# FPGA.net
KiCad netlist of a schematic drawn in Altium Designer
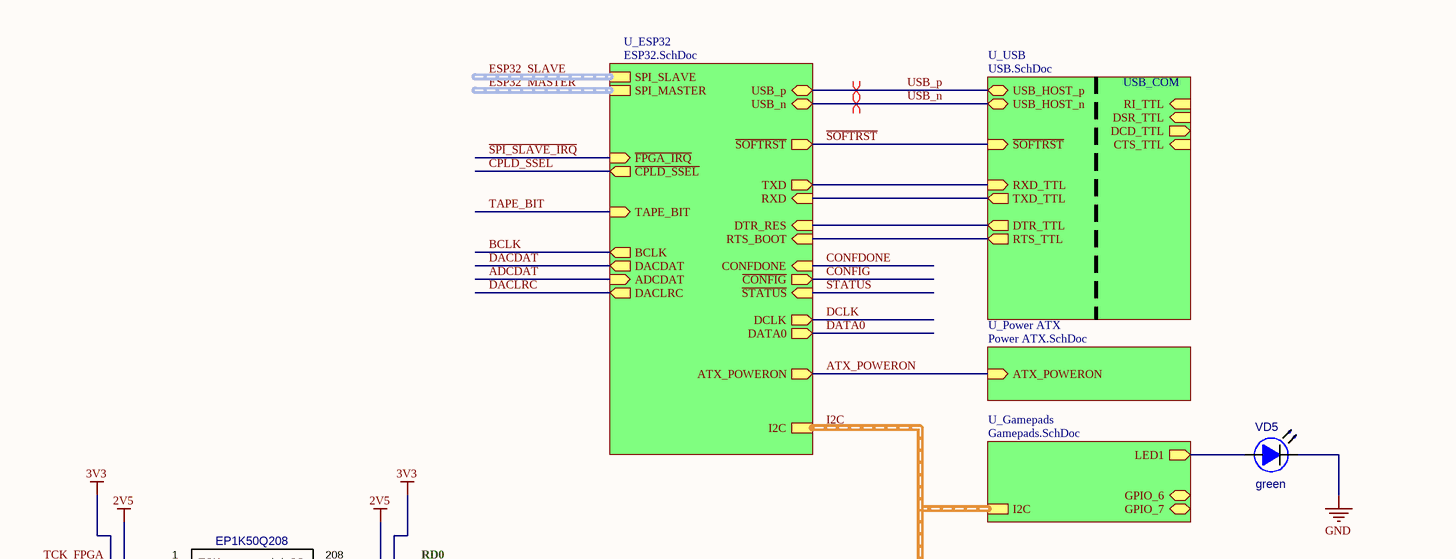
[diagram p0: FPGA.SchDoc, top]
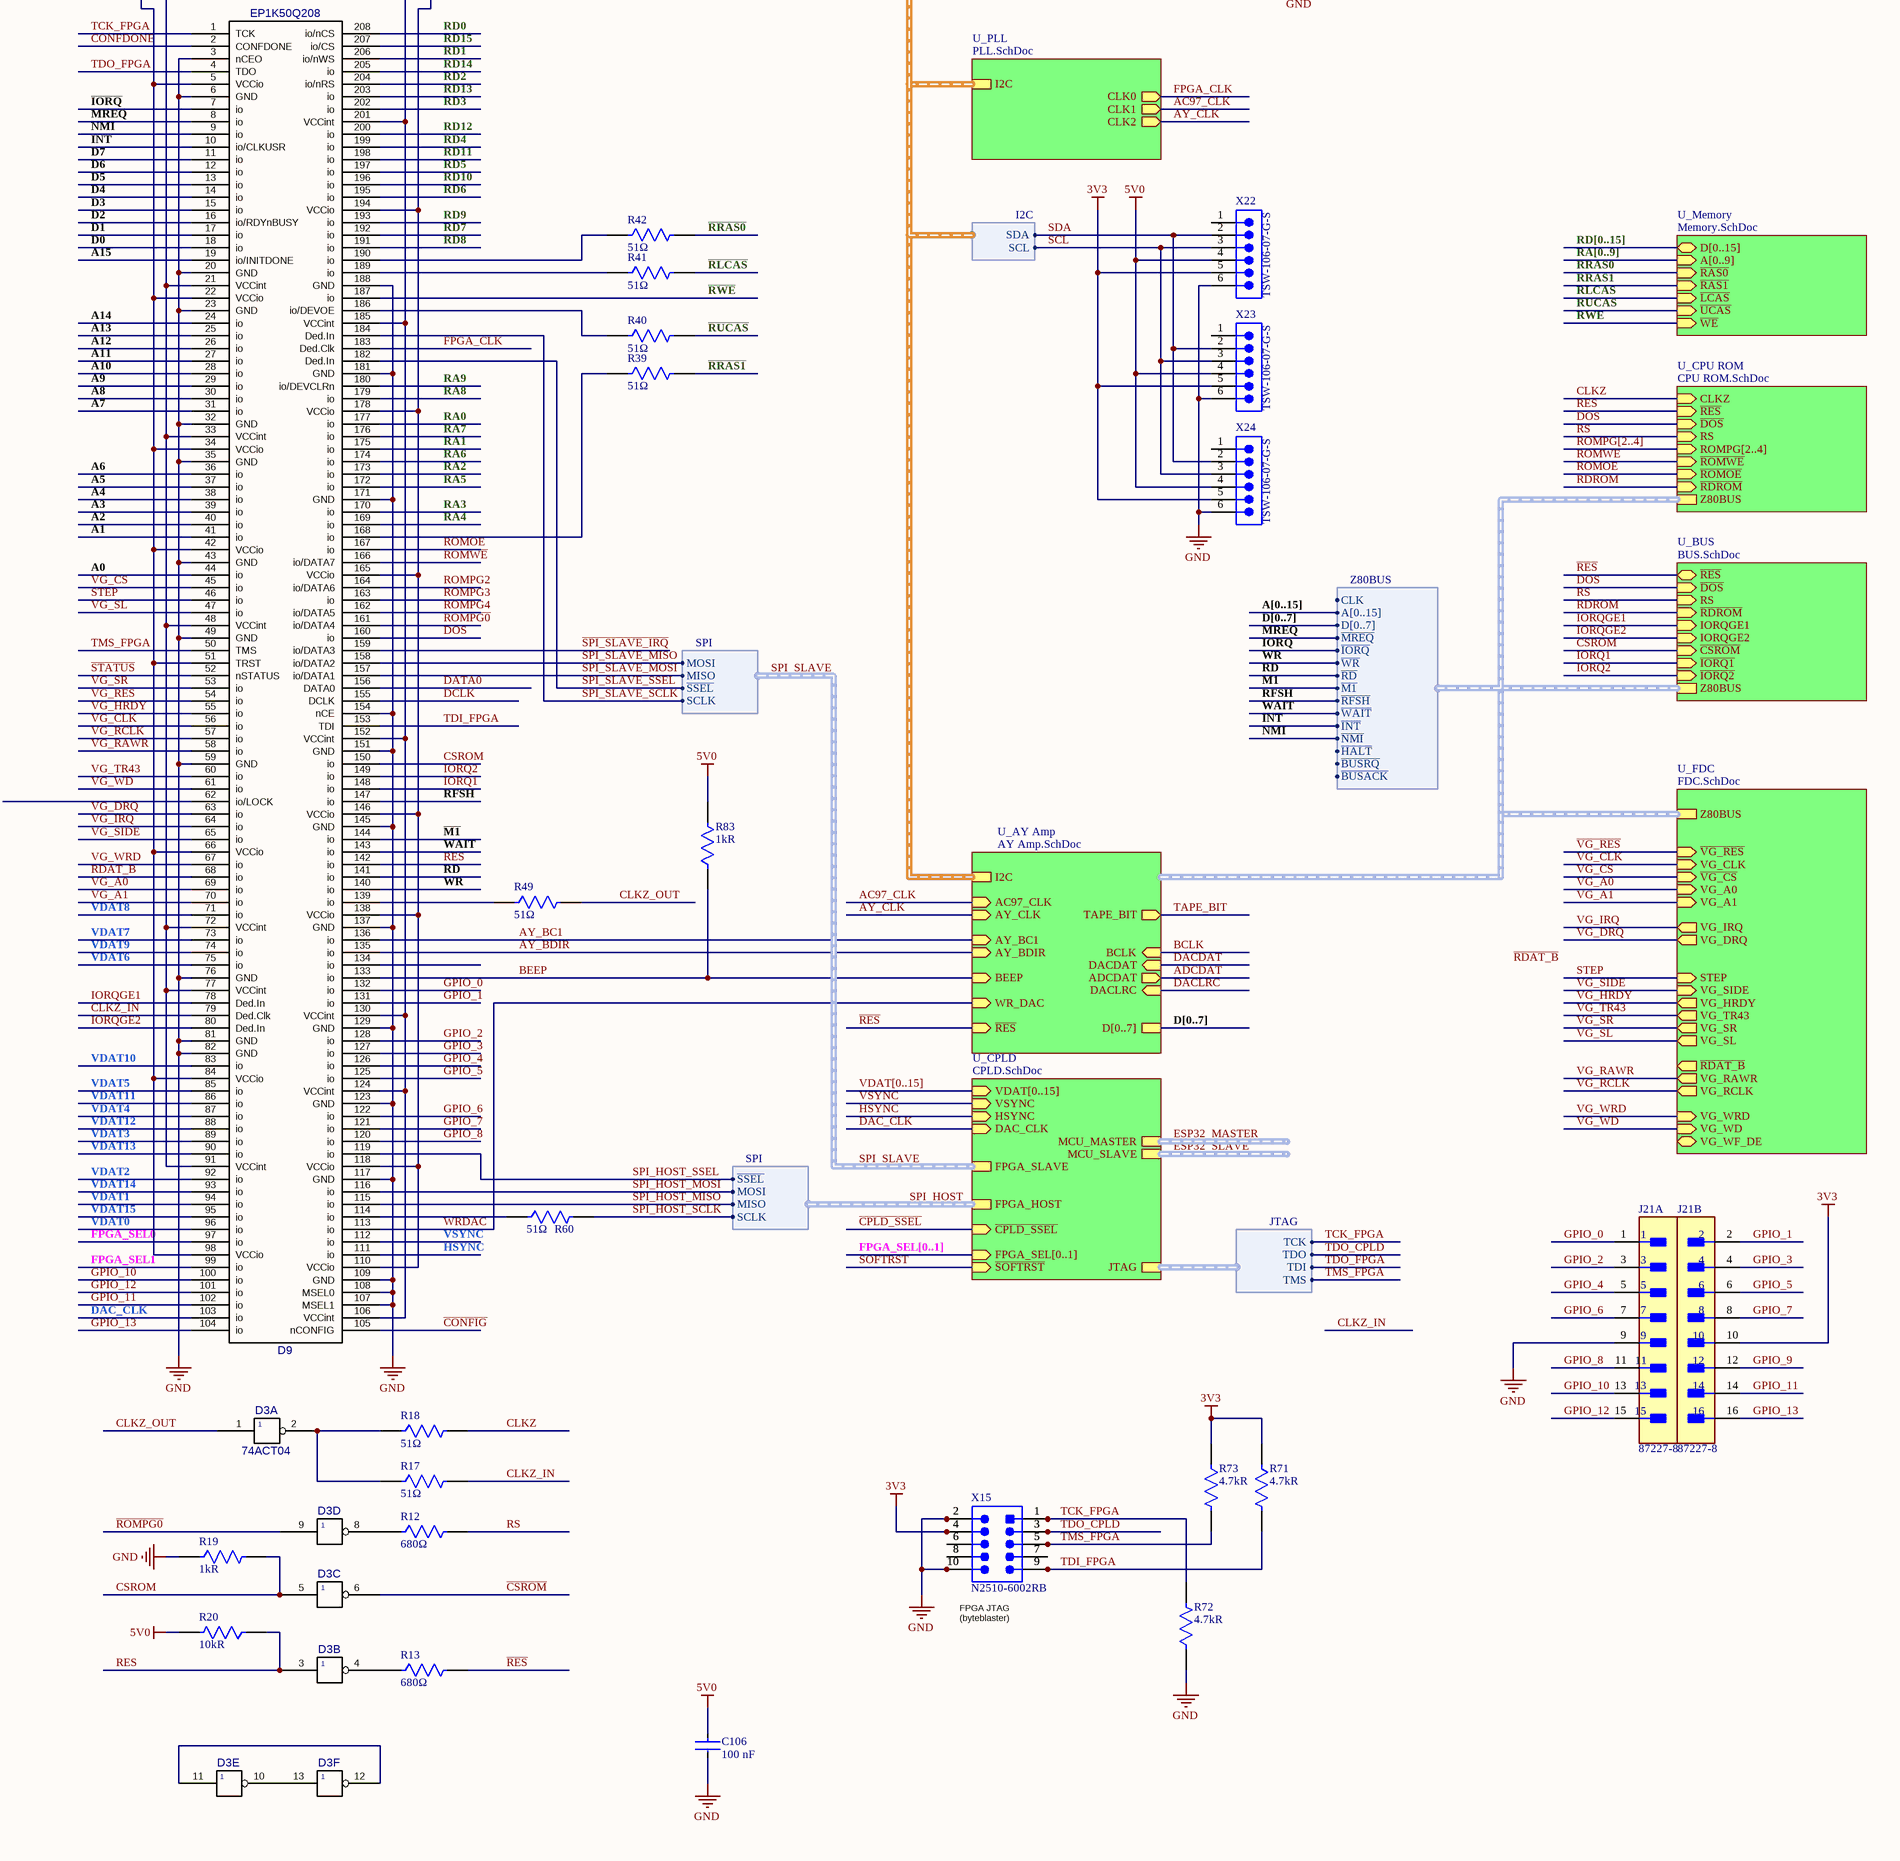
[diagram p1: FPGA.SchDoc, bottom]

(export (version "E")
  (design (tool "Eeschema 10.0.6"))
  (components
    (comp (ref "C106")
      (value "CC0805KRX7R9BB104")
      (footprint "FP-CC0805-0_85-IPC_A")
      (description "CAP CER 0.1UF 50V X7R 0805")
      (fields (field (name "CAPACITANCE") "100 nF") (field (name "MANUFACTURER") "Yageo"))
      (libsource (lib "SchLib") (part "CMP-2100-03606-3"))
    )
    (comp (ref "D3")
      (value "74ACT04")
      (footprint "SO14")
      (description "04")
      (libsource (lib "SchLib") (part "04"))
    )
    (comp (ref "D9")
      (value "EP1K50Q208")
      (footprint "PQFP208X5")
      (libsource (lib "SchLib") (part "EP1K50Q208"))
    )
    (comp (ref "J21")
      (value "87227-8")
      (footprint "FP-87227-8-MFG")
      (description "CONN HEADER VERT 16POS 2.54MM")
      (fields (field (name "MANUFACTURER") "TE Connectivity"))
      (libsource (lib "SchLib") (part "CMP-03369-000064-1"))
    )
    (comp (ref "R12")
      (value "680Ω")
      (footprint "FP-RT0805-IPC_A")
      (description "RES SMD 680 OHM 1% 1/8W 0805")
      (fields
        (field (name "MANUFACTURER") "Yageo")
        (field (name "MANUFACTURER PART NUMBER") "RT0805FRE07680RL")
      )
      (libsource (lib "SchLib") (part "CMP-03412-000082-1"))
    )
    (comp (ref "R13")
      (value "680Ω")
      (footprint "FP-RT0805-IPC_A")
      (description "RES SMD 680 OHM 1% 1/8W 0805")
      (fields
        (field (name "MANUFACTURER") "Yageo")
        (field (name "MANUFACTURER PART NUMBER") "RT0805FRE07680RL")
      )
      (libsource (lib "SchLib") (part "CMP-03412-000082-1"))
    )
    (comp (ref "R17")
      (value "RR1220Q-510-D")
      (footprint "FP-RR1220-IPC_A")
      (description "51Ω ±0.5% 0.1W 1/10W Chip Resistor 0805 (2012 Metric) Thin Film")
      (fields (field (name "RESISTANCE") "51Ω") (field (name "MANUFACTURER") "Susumu"))
      (libsource (lib "SchLib") (part "CMP-2001-03561-2"))
    )
    (comp (ref "R18")
      (value "RR1220Q-510-D")
      (footprint "FP-RR1220-IPC_A")
      (description "51Ω ±0.5% 0.1W 1/10W Chip Resistor 0805 (2012 Metric) Thin Film")
      (fields (field (name "RESISTANCE") "51Ω") (field (name "MANUFACTURER") "Susumu"))
      (libsource (lib "SchLib") (part "CMP-2001-03561-2"))
    )
    (comp (ref "R19")
      (value "CRCW08051K00FKEAHP")
      (footprint "FP-CRCW0805-HPe3-IPC_A")
      (description "RES Thick Film, 1kΩ, 1%, 0.5W, 100ppm/°C, 0805")
      (fields (field (name "RESISTANCE") "1kR") (field (name "MANUFACTURER") "Vishay Dale"))
      (libsource (lib "SchLib") (part "CMP-02407-004529-1"))
    )
    (comp (ref "R20")
      (value "CR0805-JW-103ELF")
      (footprint "FP-CR0805-IPC_A")
      (description "Thick Film Chip Resistors 0805 10kΩ 0.125W 5% 200ppm/°C")
      (fields (field (name "RESISTANCE") "10kR") (field (name "MANUFACTURER") "Bourns"))
      (libsource (lib "SchLib") (part "CMP-07231-003873-1"))
    )
    (comp (ref "R39")
      (value "RR1220Q-510-D")
      (footprint "FP-RR1220-IPC_A")
      (description "51Ω ±0.5% 0.1W 1/10W Chip Resistor 0805 (2012 Metric) Thin Film")
      (fields (field (name "RESISTANCE") "51Ω") (field (name "MANUFACTURER") "Susumu"))
      (libsource (lib "SchLib") (part "CMP-2001-03561-2"))
    )
    (comp (ref "R40")
      (value "RR1220Q-510-D")
      (footprint "FP-RR1220-IPC_A")
      (description "51Ω ±0.5% 0.1W 1/10W Chip Resistor 0805 (2012 Metric) Thin Film")
      (fields (field (name "RESISTANCE") "51Ω") (field (name "MANUFACTURER") "Susumu"))
      (libsource (lib "SchLib") (part "CMP-2001-03561-2"))
    )
    (comp (ref "R41")
      (value "RR1220Q-510-D")
      (footprint "FP-RR1220-IPC_A")
      (description "51Ω ±0.5% 0.1W 1/10W Chip Resistor 0805 (2012 Metric) Thin Film")
      (fields (field (name "RESISTANCE") "51Ω") (field (name "MANUFACTURER") "Susumu"))
      (libsource (lib "SchLib") (part "CMP-2001-03561-2"))
    )
    (comp (ref "R42")
      (value "RR1220Q-510-D")
      (footprint "FP-RR1220-IPC_A")
      (description "51Ω ±0.5% 0.1W 1/10W Chip Resistor 0805 (2012 Metric) Thin Film")
      (fields (field (name "RESISTANCE") "51Ω") (field (name "MANUFACTURER") "Susumu"))
      (libsource (lib "SchLib") (part "CMP-2001-03561-2"))
    )
    (comp (ref "R49")
      (value "RR1220Q-510-D")
      (footprint "FP-RR1220-IPC_A")
      (description "51Ω ±0.5% 0.1W 1/10W Chip Resistor 0805 (2012 Metric) Thin Film")
      (fields (field (name "RESISTANCE") "51Ω") (field (name "MANUFACTURER") "Susumu"))
      (libsource (lib "SchLib") (part "CMP-2001-03561-2"))
    )
    (comp (ref "R60")
      (value "RR1220Q-510-D")
      (footprint "FP-RR1220-IPC_A")
      (description "51Ω ±0.5% 0.1W 1/10W Chip Resistor 0805 (2012 Metric) Thin Film")
      (fields (field (name "RESISTANCE") "51Ω") (field (name "MANUFACTURER") "Susumu"))
      (libsource (lib "SchLib") (part "CMP-2001-03561-2"))
    )
    (comp (ref "R71")
      (value "CR0805-JW-472ELF")
      (footprint "FP-CR0805-IPC_A")
      (description "Thick Film Chip Resistors 0805 4.7kΩ 0.125W 5% 200ppm/°C")
      (fields (field (name "RESISTANCE") "4.7kR") (field (name "MANUFACTURER") "Bourns"))
      (libsource (lib "SchLib") (part "CMP-07231-004713-1"))
    )
    (comp (ref "R72")
      (value "CR0805-JW-472ELF")
      (footprint "FP-CR0805-IPC_A")
      (description "Thick Film Chip Resistors 0805 4.7kΩ 0.125W 5% 200ppm/°C")
      (fields (field (name "RESISTANCE") "4.7kR") (field (name "MANUFACTURER") "Bourns"))
      (libsource (lib "SchLib") (part "CMP-07231-004713-1"))
    )
    (comp (ref "R73")
      (value "CR0805-JW-472ELF")
      (footprint "FP-CR0805-IPC_A")
      (description "Thick Film Chip Resistors 0805 4.7kΩ 0.125W 5% 200ppm/°C")
      (fields (field (name "RESISTANCE") "4.7kR") (field (name "MANUFACTURER") "Bourns"))
      (libsource (lib "SchLib") (part "CMP-07231-004713-1"))
    )
    (comp (ref "R83")
      (value "CRCW08051K00FKEAHP")
      (footprint "FP-CRCW0805-HPe3-IPC_A")
      (description "RES Thick Film, 1kΩ, 1%, 0.5W, 100ppm/°C, 0805")
      (fields (field (name "RESISTANCE") "1kR") (field (name "MANUFACTURER") "Vishay Dale"))
      (libsource (lib "SchLib") (part "CMP-02407-004529-1"))
    )
    (comp (ref "VD5")
      (value "green")
      (footprint "LED100_LED(Primary)")
      (description "Light Emitting Diode")
      (fields (field (name "Comment") "LED"))
      (libsource (lib "SchLib") (part "LED"))
    )
    (comp (ref "X15")
      (value "N2510-6002RB")
      (footprint "3M-N2510-6002-10_V")
      (fields (field (name "PARTNUMBER") "N2510") (field (name "MANUFACTURER") "3M"))
      (libsource (lib "SchLib") (part "CMP-2000-06794-1"))
    )
    (comp (ref "X22")
      (value "TSW-106-07-G-S")
      (footprint "SMTC-TSW-106-07-X-S")
      (description "0.025\" SQ Post Header, Through-hole, Vertical, -55 to 125 degC, 2.54 mm Pitch, 6-Pin, Male, RoHS")
      (fields (field (name "MANUFACTURER") "Samtec"))
      (libsource (lib "SchLib") (part "CMP-1024-00383-1"))
    )
    (comp (ref "X23")
      (value "TSW-106-07-G-S")
      (footprint "SMTC-TSW-106-07-X-S")
      (description "0.025\" SQ Post Header, Through-hole, Vertical, -55 to 125 degC, 2.54 mm Pitch, 6-Pin, Male, RoHS")
      (fields (field (name "MANUFACTURER") "Samtec"))
      (libsource (lib "SchLib") (part "CMP-1024-00383-1"))
    )
    (comp (ref "X24")
      (value "TSW-106-07-G-S")
      (footprint "SMTC-TSW-106-07-X-S")
      (description "0.025\" SQ Post Header, Through-hole, Vertical, -55 to 125 degC, 2.54 mm Pitch, 6-Pin, Male, RoHS")
      (fields (field (name "MANUFACTURER") "Samtec"))
      (libsource (lib "SchLib") (part "CMP-1024-00383-1"))
    )
  )
  (nets
    (net (code "7") (name "+5v") (class "Default")
      (node (ref "D3") (pin "14") (pinfunction "+5v_14") (pintype "power_in"))
    )
    (net (code "8") (name "/A0") (class "Default")
      (node (ref "D9") (pin "44") (pinfunction "io_44") (pintype "passive"))
    )
    (net (code "9") (name "/A1") (class "Default")
      (node (ref "D9") (pin "41") (pinfunction "io_41") (pintype "passive"))
    )
    (net (code "10") (name "/A2") (class "Default")
      (node (ref "D9") (pin "40") (pinfunction "io_40") (pintype "passive"))
    )
    (net (code "11") (name "/A3") (class "Default")
      (node (ref "D9") (pin "39") (pinfunction "io_39") (pintype "passive"))
    )
    (net (code "12") (name "/A4") (class "Default")
      (node (ref "D9") (pin "38") (pinfunction "io_38") (pintype "passive"))
    )
    (net (code "13") (name "/A5") (class "Default")
      (node (ref "D9") (pin "37") (pinfunction "io_37") (pintype "passive"))
    )
    (net (code "14") (name "/A6") (class "Default")
      (node (ref "D9") (pin "36") (pinfunction "io_36") (pintype "passive"))
    )
    (net (code "15") (name "/A7") (class "Default")
      (node (ref "D9") (pin "31") (pinfunction "io_31") (pintype "passive"))
    )
    (net (code "16") (name "/A8") (class "Default")
      (node (ref "D9") (pin "30") (pinfunction "io_30") (pintype "passive"))
    )
    (net (code "17") (name "/A9") (class "Default")
      (node (ref "D9") (pin "29") (pinfunction "io_29") (pintype "passive"))
    )
    (net (code "18") (name "/A10") (class "Default")
      (node (ref "D9") (pin "28") (pinfunction "io_28") (pintype "passive"))
    )
    (net (code "19") (name "/A11") (class "Default")
      (node (ref "D9") (pin "27") (pinfunction "io_27") (pintype "passive"))
    )
    (net (code "20") (name "/A12") (class "Default")
      (node (ref "D9") (pin "26") (pinfunction "io_26") (pintype "passive"))
    )
    (net (code "21") (name "/A13") (class "Default")
      (node (ref "D9") (pin "25") (pinfunction "io_25") (pintype "passive"))
    )
    (net (code "22") (name "/A14") (class "Default")
      (node (ref "D9") (pin "24") (pinfunction "io_24") (pintype "passive"))
    )
    (net (code "23") (name "/A15") (class "Default")
      (node (ref "D9") (pin "19") (pinfunction "io/INITDONE_19") (pintype "passive"))
    )
    (net (code "27") (name "/AY_BC1") (class "Default")
      (node (ref "D9") (pin "136") (pinfunction "io_136") (pintype "passive"))
    )
    (net (code "28") (name "/AY_BDIR") (class "Default")
      (node (ref "D9") (pin "135") (pinfunction "io_135") (pintype "passive"))
    )
    (net (code "32") (name "/BEEP") (class "Default")
      (node (ref "D9") (pin "133") (pinfunction "io_133") (pintype "passive"))
      (node (ref "R83") (pin "1") (pinfunction "1_1") (pintype "passive"))
    )
    (net (code "33") (name "/CLKZ") (class "Default")
      (node (ref "R18") (pin "2") (pinfunction "2_2") (pintype "passive"))
    )
    (net (code "34") (name "/CLKZ_IN") (class "Default")
      (node (ref "D9") (pin "79") (pinfunction "Ded.Clk_79") (pintype "passive"))
      (node (ref "R17") (pin "2") (pinfunction "2_2") (pintype "passive"))
    )
    (net (code "35") (name "/CLKZ_OUT") (class "Default")
      (node (ref "D3") (pin "1") (pintype "passive"))
      (node (ref "R49") (pin "2") (pinfunction "2_2") (pintype "passive"))
    )
    (net (code "36") (name "/CONFDONE") (class "Default")
      (node (ref "D9") (pin "2") (pinfunction "CONFDONE_2") (pintype "passive"))
    )
    (net (code "37") (name "/CSROM") (class "Default")
      (node (ref "D3") (pin "5") (pintype "passive"))
      (node (ref "D9") (pin "150") (pinfunction "io_150") (pintype "passive"))
      (node (ref "R19") (pin "2") (pinfunction "2_2") (pintype "passive"))
    )
    (net (code "39") (name "/D0") (class "Default")
      (node (ref "D9") (pin "18") (pinfunction "io_18") (pintype "passive"))
    )
    (net (code "40") (name "/D1") (class "Default")
      (node (ref "D9") (pin "17") (pinfunction "io_17") (pintype "passive"))
    )
    (net (code "41") (name "/D2") (class "Default")
      (node (ref "D9") (pin "16") (pinfunction "io/RDYnBUSY_16") (pintype "passive"))
    )
    (net (code "42") (name "/D3") (class "Default")
      (node (ref "D9") (pin "15") (pinfunction "io_15") (pintype "passive"))
    )
    (net (code "43") (name "/D4") (class "Default")
      (node (ref "D9") (pin "14") (pinfunction "io_14") (pintype "passive"))
    )
    (net (code "44") (name "/D5") (class "Default")
      (node (ref "D9") (pin "13") (pinfunction "io_13") (pintype "passive"))
    )
    (net (code "45") (name "/D6") (class "Default")
      (node (ref "D9") (pin "12") (pinfunction "io_12") (pintype "passive"))
    )
    (net (code "46") (name "/D7") (class "Default")
      (node (ref "D9") (pin "11") (pinfunction "io_11") (pintype "passive"))
    )
    (net (code "49") (name "/DAC_CLK") (class "Default")
      (node (ref "D9") (pin "103") (pinfunction "io_103") (pintype "passive"))
    )
    (net (code "50") (name "/DATA0") (class "Default")
      (node (ref "D9") (pin "156") (pinfunction "DATA0_156") (pintype "passive"))
    )
    (net (code "52") (name "/DCLK") (class "Default")
      (node (ref "D9") (pin "155") (pinfunction "DCLK_155") (pintype "passive"))
    )
    (net (code "56") (name "/FPGA_CLK") (class "Default")
      (node (ref "D9") (pin "183") (pinfunction "Ded.Clk_183") (pintype "passive"))
    )
    (net (code "57") (name "/FPGA_SEL0") (class "Default")
      (node (ref "D9") (pin "97") (pinfunction "io_97") (pintype "passive"))
    )
    (net (code "58") (name "/FPGA_SEL1") (class "Default")
      (node (ref "D9") (pin "99") (pinfunction "io_99") (pintype "passive"))
    )
    (net (code "60") (name "/GPIO_0") (class "Default")
      (node (ref "D9") (pin "132") (pinfunction "io_132") (pintype "passive"))
      (node (ref "J21") (pin "1") (pinfunction "1_1") (pintype "passive"))
    )
    (net (code "61") (name "/GPIO_1") (class "Default")
      (node (ref "D9") (pin "131") (pinfunction "io_131") (pintype "passive"))
      (node (ref "J21") (pin "2") (pinfunction "2_2") (pintype "passive"))
    )
    (net (code "62") (name "/GPIO_2") (class "Default")
      (node (ref "D9") (pin "128") (pinfunction "io_128") (pintype "passive"))
      (node (ref "J21") (pin "3") (pinfunction "3_3") (pintype "passive"))
    )
    (net (code "63") (name "/GPIO_3") (class "Default")
      (node (ref "D9") (pin "127") (pinfunction "io_127") (pintype "passive"))
      (node (ref "J21") (pin "4") (pinfunction "4_4") (pintype "passive"))
    )
    (net (code "64") (name "/GPIO_4") (class "Default")
      (node (ref "D9") (pin "126") (pinfunction "io_126") (pintype "passive"))
      (node (ref "J21") (pin "5") (pinfunction "5_5") (pintype "passive"))
    )
    (net (code "65") (name "/GPIO_5") (class "Default")
      (node (ref "D9") (pin "125") (pinfunction "io_125") (pintype "passive"))
      (node (ref "J21") (pin "6") (pinfunction "6_6") (pintype "passive"))
    )
    (net (code "66") (name "/GPIO_6") (class "Default")
      (node (ref "D9") (pin "122") (pinfunction "io_122") (pintype "passive"))
      (node (ref "J21") (pin "7") (pinfunction "7_7") (pintype "passive"))
    )
    (net (code "68") (name "/GPIO_7") (class "Default")
      (node (ref "D9") (pin "121") (pinfunction "io_121") (pintype "passive"))
      (node (ref "J21") (pin "8") (pinfunction "8_8") (pintype "passive"))
    )
    (net (code "70") (name "/GPIO_8") (class "Default")
      (node (ref "D9") (pin "120") (pinfunction "io_120") (pintype "passive"))
      (node (ref "J21") (pin "11") (pinfunction "11_11") (pintype "passive"))
    )
    (net (code "71") (name "/GPIO_9") (class "Default")
      (node (ref "J21") (pin "12") (pinfunction "12_12") (pintype "passive"))
    )
    (net (code "72") (name "/GPIO_10") (class "Default")
      (node (ref "D9") (pin "100") (pinfunction "io_100") (pintype "passive"))
      (node (ref "J21") (pin "13") (pinfunction "13_13") (pintype "passive"))
    )
    (net (code "73") (name "/GPIO_11") (class "Default")
      (node (ref "D9") (pin "102") (pinfunction "io_102") (pintype "passive"))
      (node (ref "J21") (pin "14") (pinfunction "14_14") (pintype "passive"))
    )
    (net (code "74") (name "/GPIO_12") (class "Default")
      (node (ref "D9") (pin "101") (pinfunction "io_101") (pintype "passive"))
      (node (ref "J21") (pin "15") (pinfunction "15_15") (pintype "passive"))
    )
    (net (code "75") (name "/GPIO_13") (class "Default")
      (node (ref "D9") (pin "104") (pinfunction "io_104") (pintype "passive"))
      (node (ref "J21") (pin "16") (pinfunction "16_16") (pintype "passive"))
    )
    (net (code "76") (name "/HSYNC") (class "Default")
      (node (ref "D9") (pin "111") (pinfunction "io_111") (pintype "passive"))
    )
    (net (code "78") (name "/IORQGE1") (class "Default")
      (node (ref "D9") (pin "78") (pinfunction "Ded.In_78") (pintype "passive"))
    )
    (net (code "79") (name "/IORQGE2") (class "Default")
      (node (ref "D9") (pin "80") (pinfunction "Ded.In_80") (pintype "passive"))
    )
    (net (code "80") (name "/LED1") (class "Default")
      (node (ref "VD5") (pin "A") (pinfunction "A_A") (pintype "passive"))
    )
    (net (code "81") (name "/RA0") (class "Default")
      (node (ref "D9") (pin "177") (pinfunction "io_177") (pintype "passive"))
    )
    (net (code "82") (name "/RA1") (class "Default")
      (node (ref "D9") (pin "175") (pinfunction "io_175") (pintype "passive"))
    )
    (net (code "83") (name "/RA2") (class "Default")
      (node (ref "D9") (pin "173") (pinfunction "io_173") (pintype "passive"))
    )
    (net (code "84") (name "/RA3") (class "Default")
      (node (ref "D9") (pin "170") (pinfunction "io_170") (pintype "passive"))
    )
    (net (code "85") (name "/RA4") (class "Default")
      (node (ref "D9") (pin "169") (pinfunction "io_169") (pintype "passive"))
    )
    (net (code "86") (name "/RA5") (class "Default")
      (node (ref "D9") (pin "172") (pinfunction "io_172") (pintype "passive"))
    )
    (net (code "87") (name "/RA6") (class "Default")
      (node (ref "D9") (pin "174") (pinfunction "io_174") (pintype "passive"))
    )
    (net (code "88") (name "/RA7") (class "Default")
      (node (ref "D9") (pin "176") (pinfunction "io_176") (pintype "passive"))
    )
    (net (code "89") (name "/RA8") (class "Default")
      (node (ref "D9") (pin "179") (pinfunction "io_179") (pintype "passive"))
    )
    (net (code "90") (name "/RA9") (class "Default")
      (node (ref "D9") (pin "180") (pinfunction "io/DEVCLRn_180") (pintype "passive"))
    )
    (net (code "92") (name "/RD0") (class "Default")
      (node (ref "D9") (pin "208") (pinfunction "io/nCS_208") (pintype "passive"))
    )
    (net (code "93") (name "/RD1") (class "Default")
      (node (ref "D9") (pin "206") (pinfunction "io/nWS_206") (pintype "passive"))
    )
    (net (code "94") (name "/RD2") (class "Default")
      (node (ref "D9") (pin "204") (pinfunction "io/nRS_204") (pintype "passive"))
    )
    (net (code "95") (name "/RD3") (class "Default")
      (node (ref "D9") (pin "202") (pinfunction "io_202") (pintype "passive"))
    )
    (net (code "96") (name "/RD4") (class "Default")
      (node (ref "D9") (pin "199") (pinfunction "io_199") (pintype "passive"))
    )
    (net (code "97") (name "/RD5") (class "Default")
      (node (ref "D9") (pin "197") (pinfunction "io_197") (pintype "passive"))
    )
    (net (code "98") (name "/RD6") (class "Default")
      (node (ref "D9") (pin "195") (pinfunction "io_195") (pintype "passive"))
    )
    (net (code "99") (name "/RD7") (class "Default")
      (node (ref "D9") (pin "192") (pinfunction "io_192") (pintype "passive"))
    )
    (net (code "100") (name "/RD8") (class "Default")
      (node (ref "D9") (pin "191") (pinfunction "io_191") (pintype "passive"))
    )
    (net (code "101") (name "/RD9") (class "Default")
      (node (ref "D9") (pin "193") (pinfunction "io_193") (pintype "passive"))
    )
    (net (code "102") (name "/RD10") (class "Default")
      (node (ref "D9") (pin "196") (pinfunction "io_196") (pintype "passive"))
    )
    (net (code "103") (name "/RD11") (class "Default")
      (node (ref "D9") (pin "198") (pinfunction "io_198") (pintype "passive"))
    )
    (net (code "104") (name "/RD12") (class "Default")
      (node (ref "D9") (pin "200") (pinfunction "io_200") (pintype "passive"))
    )
    (net (code "105") (name "/RD13") (class "Default")
      (node (ref "D9") (pin "203") (pinfunction "io_203") (pintype "passive"))
    )
    (net (code "106") (name "/RD14") (class "Default")
      (node (ref "D9") (pin "205") (pinfunction "io_205") (pintype "passive"))
    )
    (net (code "107") (name "/RD15") (class "Default")
      (node (ref "D9") (pin "207") (pinfunction "io/CS_207") (pintype "passive"))
    )
    (net (code "109") (name "/RES") (class "Default")
      (node (ref "D3") (pin "3") (pintype "passive"))
      (node (ref "D9") (pin "142") (pinfunction "io_142") (pintype "passive"))
      (node (ref "R20") (pin "1") (pinfunction "1_1") (pintype "passive"))
    )
    (net (code "111") (name "/ROMPG2") (class "Default")
      (node (ref "D9") (pin "164") (pinfunction "io/DATA6_164") (pintype "passive"))
    )
    (net (code "112") (name "/ROMPG3") (class "Default")
      (node (ref "D9") (pin "163") (pinfunction "io_163") (pintype "passive"))
    )
    (net (code "113") (name "/ROMPG4") (class "Default")
      (node (ref "D9") (pin "162") (pinfunction "io/DATA5_162") (pintype "passive"))
    )
    (net (code "115") (name "/RS") (class "Default")
      (node (ref "R12") (pin "2") (pinfunction "2_2") (pintype "passive"))
    )
    (net (code "117") (name "/SCL") (class "Default")
      (node (ref "X22") (pin "3") (pinfunction "3_3") (pintype "passive"))
      (node (ref "X23") (pin "3") (pinfunction "3_3") (pintype "passive"))
      (node (ref "X24") (pin "3") (pinfunction "3_3") (pintype "passive"))
    )
    (net (code "118") (name "/SDA") (class "Default")
      (node (ref "X22") (pin "2") (pinfunction "2_2") (pintype "passive"))
      (node (ref "X23") (pin "2") (pinfunction "2_2") (pintype "passive"))
      (node (ref "X24") (pin "2") (pinfunction "2_2") (pintype "passive"))
    )
    (net (code "119") (name "/SPI_HOST_MISO") (class "Default")
      (node (ref "D9") (pin "115") (pinfunction "io_115") (pintype "passive"))
    )
    (net (code "120") (name "/SPI_HOST_MOSI") (class "Default")
      (node (ref "D9") (pin "116") (pinfunction "io_116") (pintype "passive"))
    )
    (net (code "121") (name "/SPI_HOST_SCLK") (class "Default")
      (node (ref "R60") (pin "2") (pinfunction "2_2") (pintype "passive"))
    )
    (net (code "122") (name "/SPI_HOST_SSEL") (class "Default")
      (node (ref "D9") (pin "119") (pinfunction "io_119") (pintype "passive"))
    )
    (net (code "124") (name "/SPI_SLAVE_MISO") (class "Default")
      (node (ref "D9") (pin "158") (pinfunction "io/DATA2_158") (pintype "passive"))
    )
    (net (code "125") (name "/SPI_SLAVE_MOSI") (class "Default")
      (node (ref "D9") (pin "157") (pinfunction "io/DATA1_157") (pintype "passive"))
    )
    (net (code "126") (name "/SPI_SLAVE_SCLK") (class "Default")
      (node (ref "D9") (pin "184") (pinfunction "Ded.In_184") (pintype "passive"))
    )
    (net (code "128") (name "/STEP") (class "Default")
      (node (ref "D9") (pin "46") (pinfunction "io_46") (pintype "passive"))
    )
    (net (code "130") (name "/TCK_FPGA") (class "Default")
      (node (ref "D9") (pin "1") (pinfunction "TCK_1") (pintype "passive"))
      (node (ref "R72") (pin "2") (pinfunction "2_2") (pintype "passive"))
      (node (ref "X15") (pin "1") (pinfunction "1_1") (pintype "passive"))
    )
    (net (code "131") (name "/TDI_FPGA") (class "Default")
      (node (ref "D9") (pin "153") (pinfunction "TDI_153") (pintype "passive"))
      (node (ref "R71") (pin "2") (pinfunction "2_2") (pintype "passive"))
      (node (ref "X15") (pin "9") (pinfunction "9_9") (pintype "passive"))
    )
    (net (code "132") (name "/TDO_CPLD") (class "Default")
      (node (ref "X15") (pin "3") (pinfunction "3_3") (pintype "passive"))
    )
    (net (code "133") (name "/TDO_FPGA") (class "Default")
      (node (ref "D9") (pin "4") (pinfunction "TDO_4") (pintype "passive"))
    )
    (net (code "134") (name "/TMS_FPGA") (class "Default")
      (node (ref "D9") (pin "50") (pinfunction "TMS_50") (pintype "passive"))
      (node (ref "R73") (pin "2") (pinfunction "2_2") (pintype "passive"))
      (node (ref "X15") (pin "5") (pinfunction "5_5") (pintype "passive"))
    )
    (net (code "139") (name "/VDAT0") (class "Default")
      (node (ref "D9") (pin "96") (pinfunction "io_96") (pintype "passive"))
    )
    (net (code "140") (name "/VDAT1") (class "Default")
      (node (ref "D9") (pin "94") (pinfunction "io_94") (pintype "passive"))
    )
    (net (code "141") (name "/VDAT2") (class "Default")
      (node (ref "D9") (pin "92") (pinfunction "io_92") (pintype "passive"))
    )
    (net (code "142") (name "/VDAT3") (class "Default")
      (node (ref "D9") (pin "89") (pinfunction "io_89") (pintype "passive"))
    )
    (net (code "143") (name "/VDAT4") (class "Default")
      (node (ref "D9") (pin "87") (pinfunction "io_87") (pintype "passive"))
    )
    (net (code "144") (name "/VDAT5") (class "Default")
      (node (ref "D9") (pin "85") (pinfunction "io_85") (pintype "passive"))
    )
    (net (code "145") (name "/VDAT6") (class "Default")
      (node (ref "D9") (pin "75") (pinfunction "io_75") (pintype "passive"))
    )
    (net (code "146") (name "/VDAT7") (class "Default")
      (node (ref "D9") (pin "73") (pinfunction "io_73") (pintype "passive"))
    )
    (net (code "147") (name "/VDAT8") (class "Default")
      (node (ref "D9") (pin "71") (pinfunction "io_71") (pintype "passive"))
    )
    (net (code "148") (name "/VDAT9") (class "Default")
      (node (ref "D9") (pin "74") (pinfunction "io_74") (pintype "passive"))
    )
    (net (code "149") (name "/VDAT10") (class "Default")
      (node (ref "D9") (pin "83") (pinfunction "io_83") (pintype "passive"))
    )
    (net (code "150") (name "/VDAT11") (class "Default")
      (node (ref "D9") (pin "86") (pinfunction "io_86") (pintype "passive"))
    )
    (net (code "151") (name "/VDAT12") (class "Default")
      (node (ref "D9") (pin "88") (pinfunction "io_88") (pintype "passive"))
    )
    (net (code "152") (name "/VDAT13") (class "Default")
      (node (ref "D9") (pin "90") (pinfunction "io_90") (pintype "passive"))
    )
    (net (code "153") (name "/VDAT14") (class "Default")
      (node (ref "D9") (pin "93") (pinfunction "io_93") (pintype "passive"))
    )
    (net (code "154") (name "/VDAT15") (class "Default")
      (node (ref "D9") (pin "95") (pinfunction "io_95") (pintype "passive"))
    )
    (net (code "156") (name "/VG_A0") (class "Default")
      (node (ref "D9") (pin "69") (pinfunction "io_69") (pintype "passive"))
    )
    (net (code "157") (name "/VG_A1") (class "Default")
      (node (ref "D9") (pin "70") (pinfunction "io_70") (pintype "passive"))
    )
    (net (code "158") (name "/VG_CLK") (class "Default")
      (node (ref "D9") (pin "56") (pinfunction "io_56") (pintype "passive"))
    )
    (net (code "159") (name "/VG_DRQ") (class "Default")
      (node (ref "D9") (pin "63") (pinfunction "io_63") (pintype "passive"))
    )
    (net (code "160") (name "/VG_HRDY") (class "Default")
      (node (ref "D9") (pin "55") (pinfunction "io_55") (pintype "passive"))
    )
    (net (code "161") (name "/VG_IRQ") (class "Default")
      (node (ref "D9") (pin "64") (pinfunction "io_64") (pintype "passive"))
    )
    (net (code "162") (name "/VG_RAWR") (class "Default")
      (node (ref "D9") (pin "58") (pinfunction "io_58") (pintype "passive"))
    )
    (net (code "163") (name "/VG_RCLK") (class "Default")
      (node (ref "D9") (pin "57") (pinfunction "io_57") (pintype "passive"))
    )
    (net (code "164") (name "/VG_SIDE") (class "Default")
      (node (ref "D9") (pin "65") (pinfunction "io_65") (pintype "passive"))
    )
    (net (code "165") (name "/VG_SL") (class "Default")
      (node (ref "D9") (pin "47") (pinfunction "io_47") (pintype "passive"))
    )
    (net (code "166") (name "/VG_SR") (class "Default")
      (node (ref "D9") (pin "53") (pinfunction "io_53") (pintype "passive"))
    )
    (net (code "167") (name "/VG_TR43") (class "Default")
      (node (ref "D9") (pin "60") (pinfunction "io_60") (pintype "passive"))
    )
    (net (code "168") (name "/VG_WD") (class "Default")
      (node (ref "D9") (pin "61") (pinfunction "io_61") (pintype "passive"))
    )
    (net (code "170") (name "/VG_WRD") (class "Default")
      (node (ref "D9") (pin "67") (pinfunction "io_67") (pintype "passive"))
    )
    (net (code "171") (name "/VSYNC") (class "Default")
      (node (ref "D9") (pin "112") (pinfunction "io_112") (pintype "passive"))
    )
    (net (code "172") (name "/WRDAC") (class "Default")
      (node (ref "D9") (pin "113") (pinfunction "io_113") (pintype "passive"))
    )
    (net (code "178") (name "/~{CONFIG}") (class "Default")
      (node (ref "D9") (pin "105") (pinfunction "nCONFIG_105") (pintype "passive"))
    )
    (net (code "180") (name "/~{CSROM}") (class "Default") (node (ref "D3") (pin "6") (pintype "passive")))
    (net (code "181") (name "/~{DOS}") (class "Default")
      (node (ref "D9") (pin "160") (pinfunction "io_160") (pintype "passive"))
    )
    (net (code "182") (name "/~{INT}") (class "Default")
      (node (ref "D9") (pin "10") (pinfunction "io/CLKUSR_10") (pintype "passive"))
    )
    (net (code "183") (name "/~{IORQ1}") (class "Default")
      (node (ref "D9") (pin "148") (pinfunction "io_148") (pintype "passive"))
    )
    (net (code "184") (name "/~{IORQ2}") (class "Default")
      (node (ref "D9") (pin "149") (pinfunction "io_149") (pintype "passive"))
    )
    (net (code "185") (name "/~{IORQ}") (class "Default")
      (node (ref "D9") (pin "7") (pinfunction "io_7") (pintype "passive"))
    )
    (net (code "186") (name "/~{M1}") (class "Default")
      (node (ref "D9") (pin "144") (pinfunction "io_144") (pintype "passive"))
    )
    (net (code "187") (name "/~{MREQ}") (class "Default")
      (node (ref "D9") (pin "8") (pinfunction "io_8") (pintype "passive"))
    )
    (net (code "188") (name "/~{NMI}") (class "Default")
      (node (ref "D9") (pin "9") (pinfunction "io_9") (pintype "passive"))
    )
    (net (code "189") (name "/~{RDAT_B}") (class "Default")
      (node (ref "D9") (pin "68") (pinfunction "io_68") (pintype "passive"))
    )
    (net (code "192") (name "/~{RD}") (class "Default")
      (node (ref "D9") (pin "141") (pinfunction "io_141") (pintype "passive"))
    )
    (net (code "193") (name "/~{RES}") (class "Default")
      (node (ref "R13") (pin "2") (pinfunction "2_2") (pintype "passive"))
    )
    (net (code "194") (name "/~{RFSH}") (class "Default")
      (node (ref "D9") (pin "147") (pinfunction "io_147") (pintype "passive"))
    )
    (net (code "195") (name "/~{RLCAS}") (class "Default")
      (node (ref "R41") (pin "2") (pinfunction "2_2") (pintype "passive"))
    )
    (net (code "196") (name "/~{ROMOE}") (class "Default")
      (node (ref "D9") (pin "167") (pinfunction "io_167") (pintype "passive"))
    )
    (net (code "197") (name "/~{ROMPG0}") (class "Default")
      (node (ref "D3") (pin "9") (pintype "passive"))
      (node (ref "D9") (pin "161") (pinfunction "io/DATA4_161") (pintype "passive"))
    )
    (net (code "198") (name "/~{ROMWE}") (class "Default")
      (node (ref "D9") (pin "166") (pinfunction "io/DATA7_166") (pintype "passive"))
    )
    (net (code "199") (name "/~{RRAS0}") (class "Default")
      (node (ref "R42") (pin "2") (pinfunction "2_2") (pintype "passive"))
    )
    (net (code "200") (name "/~{RRAS1}") (class "Default")
      (node (ref "R39") (pin "2") (pinfunction "2_2") (pintype "passive"))
    )
    (net (code "201") (name "/~{RUCAS}") (class "Default")
      (node (ref "R40") (pin "2") (pinfunction "2_2") (pintype "passive"))
    )
    (net (code "202") (name "/~{RWE}") (class "Default")
      (node (ref "D9") (pin "187") (pinfunction "io_187") (pintype "passive"))
    )
    (net (code "204") (name "/~{SPI_SLAVE_IRQ}") (class "Default")
      (node (ref "D9") (pin "159") (pinfunction "io/DATA3_159") (pintype "passive"))
    )
    (net (code "205") (name "/~{SPI_SLAVE_SSEL}") (class "Default")
      (node (ref "D9") (pin "182") (pinfunction "Ded.In_182") (pintype "passive"))
    )
    (net (code "206") (name "/~{STATUS}") (class "Default")
      (node (ref "D9") (pin "52") (pinfunction "nSTATUS_52") (pintype "passive"))
    )
    (net (code "207") (name "/~{VG_CS}") (class "Default")
      (node (ref "D9") (pin "45") (pinfunction "io_45") (pintype "passive"))
    )
    (net (code "208") (name "/~{VG_RES}") (class "Default")
      (node (ref "D9") (pin "54") (pinfunction "io_54") (pintype "passive"))
    )
    (net (code "209") (name "/~{WAIT}") (class "Default")
      (node (ref "D9") (pin "143") (pinfunction "io_143") (pintype "passive"))
    )
    (net (code "210") (name "/~{WR}") (class "Default")
      (node (ref "D9") (pin "140") (pinfunction "io_140") (pintype "passive"))
    )
    (net (code "211") (name "2V5") (class "Default")
      (node (ref "D9") (pin "106") (pinfunction "VCCint_106") (pintype "passive"))
      (node (ref "D9") (pin "124") (pinfunction "VCCint_124") (pintype "passive"))
      (node (ref "D9") (pin "130") (pinfunction "VCCint_130") (pintype "passive"))
      (node (ref "D9") (pin "152") (pinfunction "VCCint_152") (pintype "passive"))
      (node (ref "D9") (pin "185") (pinfunction "VCCint_185") (pintype "passive"))
      (node (ref "D9") (pin "201") (pinfunction "VCCint_201") (pintype "passive"))
      (node (ref "D9") (pin "21") (pinfunction "VCCint_21") (pintype "passive"))
      (node (ref "D9") (pin "33") (pinfunction "VCCint_33") (pintype "passive"))
      (node (ref "D9") (pin "48") (pinfunction "VCCint_48") (pintype "passive"))
      (node (ref "D9") (pin "72") (pinfunction "VCCint_72") (pintype "passive"))
      (node (ref "D9") (pin "77") (pinfunction "VCCint_77") (pintype "passive"))
      (node (ref "D9") (pin "91") (pinfunction "VCCint_91") (pintype "passive"))
    )
    (net (code "212") (name "3V3") (class "Default")
      (node (ref "D9") (pin "110") (pinfunction "VCCio_110") (pintype "passive"))
      (node (ref "D9") (pin "118") (pinfunction "VCCio_118") (pintype "passive"))
      (node (ref "D9") (pin "138") (pinfunction "VCCio_138") (pintype "passive"))
      (node (ref "D9") (pin "146") (pinfunction "VCCio_146") (pintype "passive"))
      (node (ref "D9") (pin "165") (pinfunction "VCCio_165") (pintype "passive"))
      (node (ref "D9") (pin "178") (pinfunction "VCCio_178") (pintype "passive"))
      (node (ref "D9") (pin "194") (pinfunction "VCCio_194") (pintype "passive"))
      (node (ref "D9") (pin "22") (pinfunction "VCCio_22") (pintype "passive"))
      (node (ref "D9") (pin "34") (pinfunction "VCCio_34") (pintype "passive"))
      (node (ref "D9") (pin "42") (pinfunction "VCCio_42") (pintype "passive"))
      (node (ref "D9") (pin "5") (pinfunction "VCCio_5") (pintype "passive"))
      (node (ref "D9") (pin "51") (pinfunction "TRST_51") (pintype "passive"))
      (node (ref "D9") (pin "66") (pinfunction "VCCio_66") (pintype "passive"))
      (node (ref "D9") (pin "84") (pinfunction "VCCio_84") (pintype "passive"))
      (node (ref "D9") (pin "98") (pinfunction "VCCio_98") (pintype "passive"))
      (node (ref "J21") (pin "10") (pinfunction "10_10") (pintype "passive"))
      (node (ref "R71") (pin "1") (pinfunction "1_1") (pintype "passive"))
      (node (ref "R73") (pin "1") (pinfunction "1_1") (pintype "passive"))
      (node (ref "X15") (pin "4") (pinfunction "4_4") (pintype "passive"))
      (node (ref "X22") (pin "5") (pinfunction "5_5") (pintype "passive"))
      (node (ref "X23") (pin "5") (pinfunction "5_5") (pintype "passive"))
      (node (ref "X24") (pin "5") (pinfunction "5_5") (pintype "passive"))
    )
    (net (code "213") (name "5V0") (class "Default")
      (node (ref "C106") (pin "1") (pinfunction "1_1") (pintype "passive"))
      (node (ref "R20") (pin "2") (pinfunction "2_2") (pintype "passive"))
      (node (ref "R83") (pin "2") (pinfunction "2_2") (pintype "passive"))
      (node (ref "X22") (pin "4") (pinfunction "4_4") (pintype "passive"))
      (node (ref "X23") (pin "4") (pinfunction "4_4") (pintype "passive"))
      (node (ref "X24") (pin "4") (pinfunction "4_4") (pintype "passive"))
    )
    (net (code "214") (name "GND") (class "Default")
      (node (ref "C106") (pin "2") (pinfunction "2_2") (pintype "passive"))
      (node (ref "D3") (pin "7") (pinfunction "GND_7") (pintype "power_in"))
      (node (ref "D9") (pin "107") (pinfunction "MSEL1_107") (pintype "passive"))
      (node (ref "D9") (pin "108") (pinfunction "MSEL0_108") (pintype "passive"))
      (node (ref "D9") (pin "109") (pinfunction "GND_109") (pintype "passive"))
      (node (ref "D9") (pin "117") (pinfunction "GND_117") (pintype "passive"))
      (node (ref "D9") (pin "123") (pinfunction "GND_123") (pintype "passive"))
      (node (ref "D9") (pin "129") (pinfunction "GND_129") (pintype "passive"))
      (node (ref "D9") (pin "137") (pinfunction "GND_137") (pintype "passive"))
      (node (ref "D9") (pin "145") (pinfunction "GND_145") (pintype "passive"))
      (node (ref "D9") (pin "151") (pinfunction "GND_151") (pintype "passive"))
      (node (ref "D9") (pin "154") (pinfunction "nCE_154") (pintype "passive"))
      (node (ref "D9") (pin "171") (pinfunction "GND_171") (pintype "passive"))
      (node (ref "D9") (pin "181") (pinfunction "GND_181") (pintype "passive"))
      (node (ref "D9") (pin "188") (pinfunction "GND_188") (pintype "passive"))
      (node (ref "D9") (pin "20") (pinfunction "GND_20") (pintype "passive"))
      (node (ref "D9") (pin "23") (pinfunction "GND_23") (pintype "passive"))
      (node (ref "D9") (pin "3") (pinfunction "nCEO_3") (pintype "passive"))
      (node (ref "D9") (pin "32") (pinfunction "GND_32") (pintype "passive"))
      (node (ref "D9") (pin "35") (pinfunction "GND_35") (pintype "passive"))
      (node (ref "D9") (pin "43") (pinfunction "GND_43") (pintype "passive"))
      (node (ref "D9") (pin "49") (pinfunction "GND_49") (pintype "passive"))
      (node (ref "D9") (pin "59") (pinfunction "GND_59") (pintype "passive"))
      (node (ref "D9") (pin "6") (pinfunction "GND_6") (pintype "passive"))
      (node (ref "D9") (pin "76") (pinfunction "GND_76") (pintype "passive"))
      (node (ref "D9") (pin "81") (pinfunction "GND_81") (pintype "passive"))
      (node (ref "D9") (pin "82") (pinfunction "GND_82") (pintype "passive"))
      (node (ref "J21") (pin "9") (pinfunction "9_9") (pintype "passive"))
      (node (ref "R19") (pin "1") (pinfunction "1_1") (pintype "passive"))
      (node (ref "R72") (pin "1") (pinfunction "1_1") (pintype "passive"))
      (node (ref "VD5") (pin "K") (pinfunction "K_K") (pintype "passive"))
      (node (ref "X15") (pin "10") (pinfunction "10_10") (pintype "passive"))
      (node (ref "X15") (pin "2") (pinfunction "2_2") (pintype "passive"))
      (node (ref "X22") (pin "6") (pinfunction "6_6") (pintype "passive"))
      (node (ref "X23") (pin "6") (pinfunction "6_6") (pintype "passive"))
      (node (ref "X24") (pin "6") (pinfunction "6_6") (pintype "passive"))
    )
    (net (code "215") (name "Net-(D3-Pad2)") (class "Default")
      (node (ref "D3") (pin "2") (pintype "passive"))
      (node (ref "R17") (pin "1") (pinfunction "1_1") (pintype "passive"))
      (node (ref "R18") (pin "1") (pinfunction "1_1") (pintype "passive"))
    )
    (net (code "216") (name "Net-(D3-Pad4)") (class "Default")
      (node (ref "D3") (pin "4") (pintype "passive"))
      (node (ref "R13") (pin "1") (pinfunction "1_1") (pintype "passive"))
    )
    (net (code "217") (name "Net-(D3-Pad8)") (class "Default")
      (node (ref "D3") (pin "8") (pintype "passive"))
      (node (ref "R12") (pin "1") (pinfunction "1_1") (pintype "passive"))
    )
    (net (code "218") (name "Net-(D3-Pad10)") (class "Default")
      (node (ref "D3") (pin "10") (pintype "passive"))
      (node (ref "D3") (pin "13") (pintype "passive"))
    )
    (net (code "219") (name "Net-(D3-Pad11)") (class "Default")
      (node (ref "D3") (pin "11") (pintype "passive"))
      (node (ref "D3") (pin "12") (pintype "passive"))
    )
    (net (code "220") (name "Net-(D9-io-Pad114)") (class "Default")
      (node (ref "D9") (pin "114") (pinfunction "io_114") (pintype "passive"))
      (node (ref "R60") (pin "1") (pinfunction "1_1") (pintype "passive"))
    )
    (net (code "221") (name "Net-(D9-io-Pad139)") (class "Default")
      (node (ref "D9") (pin "139") (pinfunction "io_139") (pintype "passive"))
      (node (ref "R49") (pin "1") (pinfunction "1_1") (pintype "passive"))
    )
    (net (code "222") (name "Net-(D9-io-Pad168)") (class "Default")
      (node (ref "D9") (pin "168") (pinfunction "io_168") (pintype "passive"))
      (node (ref "R39") (pin "1") (pinfunction "1_1") (pintype "passive"))
    )
    (net (code "223") (name "Net-(D9-io-Pad189)") (class "Default")
      (node (ref "D9") (pin "189") (pinfunction "io_189") (pintype "passive"))
      (node (ref "R41") (pin "1") (pinfunction "1_1") (pintype "passive"))
    )
    (net (code "224") (name "Net-(D9-io-Pad190)") (class "Default")
      (node (ref "D9") (pin "190") (pinfunction "io_190") (pintype "passive"))
      (node (ref "R42") (pin "1") (pinfunction "1_1") (pintype "passive"))
    )
    (net (code "225") (name "Net-(D9-io{slash}DEVOE)") (class "Default")
      (node (ref "D9") (pin "186") (pinfunction "io/DEVOE_186") (pintype "passive"))
      (node (ref "R40") (pin "1") (pinfunction "1_1") (pintype "passive"))
    )
    (net (code "226") (name "Net-(X15-Pad6)") (class "Default")
      (node (ref "X15") (pin "6") (pinfunction "6_6") (pintype "passive"))
    )
    (net (code "227") (name "Net-(X15-Pad7)") (class "Default")
      (node (ref "X15") (pin "7") (pinfunction "7_7") (pintype "passive"))
    )
    (net (code "228") (name "Net-(X15-Pad8)") (class "Default")
      (node (ref "X15") (pin "8") (pinfunction "8_8") (pintype "passive"))
    )
    (net (code "229") (name "unconnected-(D9-io-Pad134)") (class "Default")
      (node (ref "D9") (pin "134") (pinfunction "io_134") (pintype "passive"))
    )
    (net (code "230") (name "unconnected-(D9-io{slash}LOCK-Pad62)") (class "Default")
      (node (ref "D9") (pin "62") (pinfunction "io/LOCK_62") (pintype "passive"))
    )
    (net (code "231") (name "unconnected-(X22-Pad1)") (class "Default")
      (node (ref "X22") (pin "1") (pinfunction "1_1") (pintype "passive"))
    )
    (net (code "232") (name "unconnected-(X23-Pad1)") (class "Default")
      (node (ref "X23") (pin "1") (pinfunction "1_1") (pintype "passive"))
    )
    (net (code "233") (name "unconnected-(X24-Pad1)") (class "Default")
      (node (ref "X24") (pin "1") (pinfunction "1_1") (pintype "passive"))
    )
  )
)
